# RF_Front_End.net
KiCad netlist of a schematic drawn in Altium Designer
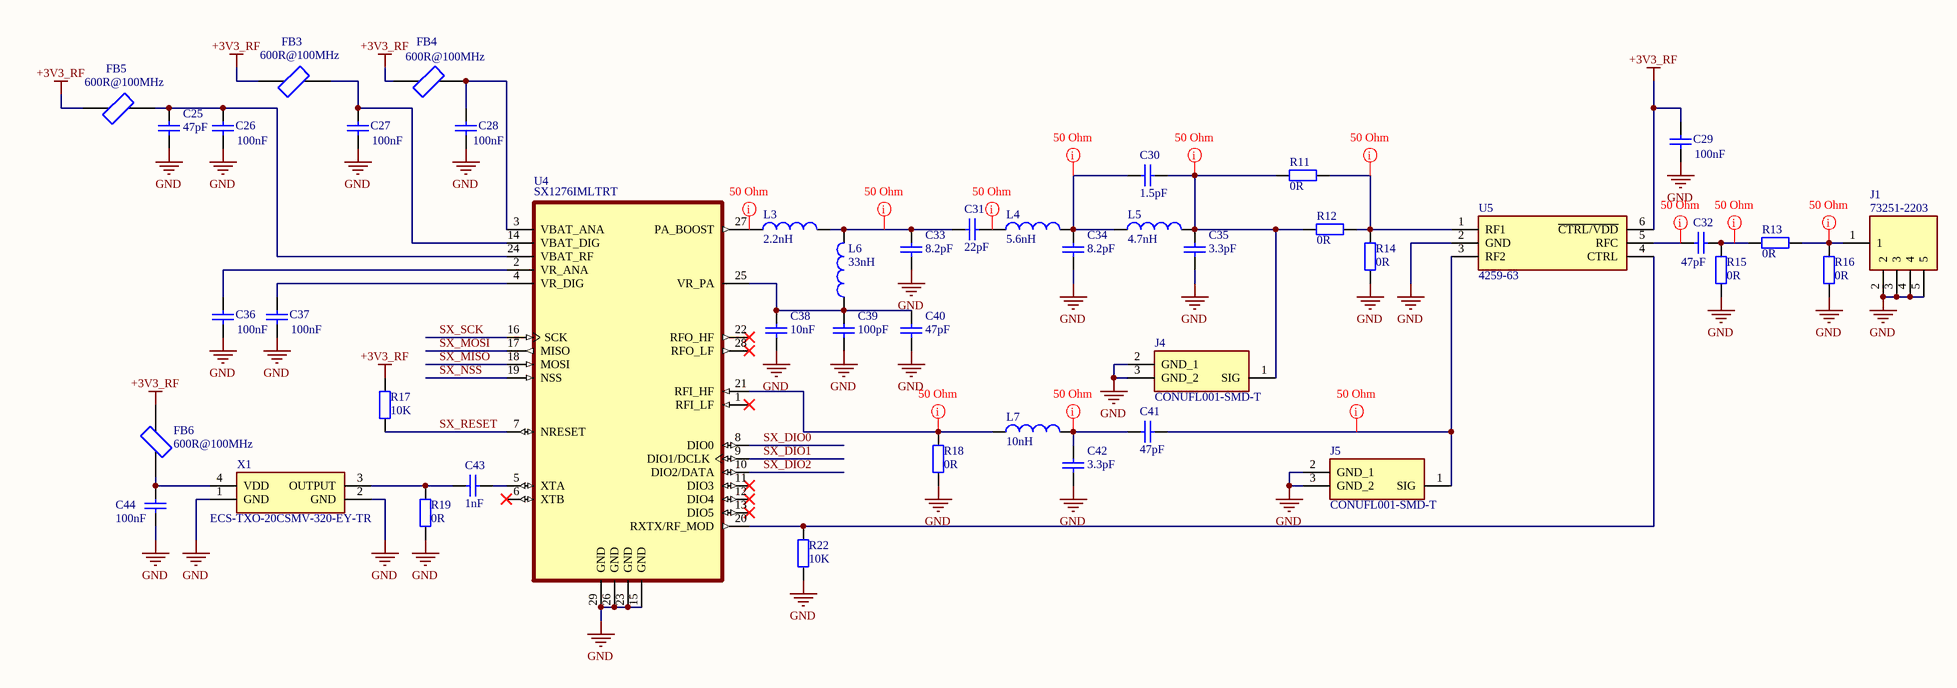
[diagram p0: RF Front End.SchDoc]

(export (version "E")
  (design (tool "Eeschema 10.0.6"))
  (components
    (comp (ref "C25")
      (value "47pF")
      (footprint "SMD-0402C")
      (description "Capacitor")
      (fields (field (name "PUBLISHER") "Altium Limited"))
      (libsource (lib "Miscellaneous Devices") (part "Cap"))
    )
    (comp (ref "C26")
      (value "100nF")
      (footprint "SMD-0402C")
      (description "Capacitor")
      (fields (field (name "PUBLISHER") "Altium Limited"))
      (libsource (lib "Miscellaneous Devices") (part "Cap"))
    )
    (comp (ref "C27")
      (value "100nF")
      (footprint "SMD-0402C")
      (description "Capacitor")
      (fields (field (name "PUBLISHER") "Altium Limited"))
      (libsource (lib "Miscellaneous Devices") (part "Cap"))
    )
    (comp (ref "C28")
      (value "100nF")
      (footprint "SMD-0402C")
      (description "Capacitor")
      (fields (field (name "PUBLISHER") "Altium Limited"))
      (libsource (lib "Miscellaneous Devices") (part "Cap"))
    )
    (comp (ref "C29")
      (value "100nF")
      (footprint "SMD-0402C")
      (description "Capacitor")
      (fields (field (name "PUBLISHER") "Altium Limited"))
      (libsource (lib "Miscellaneous Devices") (part "Cap"))
    )
    (comp (ref "C30")
      (value "1.5pF")
      (footprint "SMD-0402C")
      (description "Capacitor")
      (fields (field (name "PUBLISHER") "Altium Limited"))
      (libsource (lib "Miscellaneous Devices") (part "Cap"))
    )
    (comp (ref "C31")
      (value "22pF")
      (footprint "SMD-0402C")
      (description "Capacitor")
      (fields (field (name "PUBLISHER") "Altium Limited"))
      (libsource (lib "Miscellaneous Devices") (part "Cap"))
    )
    (comp (ref "C32")
      (value "47pF")
      (footprint "SMD-0402C")
      (description "Capacitor")
      (fields (field (name "PUBLISHER") "Altium Limited"))
      (libsource (lib "Miscellaneous Devices") (part "Cap"))
    )
    (comp (ref "C33")
      (value "8.2pF")
      (footprint "SMD-0402C")
      (description "Capacitor")
      (fields (field (name "PUBLISHER") "Altium Limited"))
      (libsource (lib "Miscellaneous Devices") (part "Cap"))
    )
    (comp (ref "C34")
      (value "8.2pF")
      (footprint "SMD-0402C")
      (description "Capacitor")
      (fields (field (name "PUBLISHER") "Altium Limited"))
      (libsource (lib "Miscellaneous Devices") (part "Cap"))
    )
    (comp (ref "C35")
      (value "3.3pF")
      (footprint "SMD-0402C")
      (description "Capacitor")
      (fields (field (name "PUBLISHER") "Altium Limited"))
      (libsource (lib "Miscellaneous Devices") (part "Cap"))
    )
    (comp (ref "C36")
      (value "100nF")
      (footprint "SMD-0402C")
      (description "Capacitor")
      (fields (field (name "PUBLISHER") "Altium Limited"))
      (libsource (lib "Miscellaneous Devices") (part "Cap"))
    )
    (comp (ref "C37")
      (value "100nF")
      (footprint "SMD-0402C")
      (description "Capacitor")
      (fields (field (name "PUBLISHER") "Altium Limited"))
      (libsource (lib "Miscellaneous Devices") (part "Cap"))
    )
    (comp (ref "C38")
      (value "10nF")
      (footprint "SMD-0402C")
      (description "Capacitor")
      (fields (field (name "PUBLISHER") "Altium Limited"))
      (libsource (lib "Miscellaneous Devices") (part "Cap"))
    )
    (comp (ref "C39")
      (value "100pF")
      (footprint "SMD-0402C")
      (description "Capacitor")
      (fields (field (name "PUBLISHER") "Altium Limited"))
      (libsource (lib "Miscellaneous Devices") (part "Cap"))
    )
    (comp (ref "C40")
      (value "47pF")
      (footprint "SMD-0402C")
      (description "Capacitor")
      (fields (field (name "PUBLISHER") "Altium Limited"))
      (libsource (lib "Miscellaneous Devices") (part "Cap"))
    )
    (comp (ref "C41")
      (value "47pF")
      (footprint "SMD-0402C")
      (description "Capacitor")
      (fields (field (name "PUBLISHER") "Altium Limited"))
      (libsource (lib "Miscellaneous Devices") (part "Cap"))
    )
    (comp (ref "C42")
      (value "3.3pF")
      (footprint "SMD-0402C")
      (description "Capacitor")
      (fields (field (name "PUBLISHER") "Altium Limited"))
      (libsource (lib "Miscellaneous Devices") (part "Cap"))
    )
    (comp (ref "C43")
      (value "1nF")
      (footprint "SMD-0402C")
      (description "Capacitor")
      (fields (field (name "PUBLISHER") "Altium Limited"))
      (libsource (lib "Miscellaneous Devices") (part "Cap"))
    )
    (comp (ref "C44")
      (value "100nF")
      (footprint "SMD-0402C")
      (description "Capacitor")
      (fields (field (name "PUBLISHER") "Altium Limited"))
      (libsource (lib "Miscellaneous Devices") (part "Cap"))
    )
    (comp (ref "FB3")
      (value "600R@100MHz")
      (footprint "0402 Ferrite Bead")
      (description "Ferrite Beads FERRITE BEAD 600 OHM 0402 1LN")
      (fields (field (name "MF") "Laird-Signal Integrity Products") (field (name "MP") "MI0805K400R-10"))
      (libsource (lib "Schematic_library") (part "Ferrite"))
    )
    (comp (ref "FB4")
      (value "600R@100MHz")
      (footprint "0402 Ferrite Bead")
      (description "Ferrite Beads FERRITE BEAD 600 OHM 0402 1LN")
      (fields (field (name "MF") "Laird-Signal Integrity Products") (field (name "MP") "MI0805K400R-10"))
      (libsource (lib "Schematic_library") (part "Ferrite"))
    )
    (comp (ref "FB5")
      (value "600R@100MHz")
      (footprint "0402 Ferrite Bead")
      (description "Ferrite Beads FERRITE BEAD 600 OHM 0402 1LN")
      (fields (field (name "MF") "Laird-Signal Integrity Products") (field (name "MP") "MI0805K400R-10"))
      (libsource (lib "Schematic_library") (part "Ferrite"))
    )
    (comp (ref "FB6")
      (value "600R@100MHz")
      (footprint "0402 Ferrite Bead")
      (description "Ferrite Beads FERRITE BEAD 600 OHM 0402 1LN")
      (fields (field (name "MF") "Laird-Signal Integrity Products") (field (name "MP") "MI0805K400R-10"))
      (libsource (lib "Schematic_library") (part "Ferrite"))
    )
    (comp (ref "J1")
      (value "73251-2203")
      (footprint "732512203")
      (description "RF Connectors / Coaxial Connectors Conn 50 Ohms, SMA Jack, Right-Angle PCB, Gold")
      (fields (field (name "MOUSER PART NUMBER") "538-73251-2203"))
      (libsource (lib "Schematic_library") (part "73251-2203"))
    )
    (comp (ref "J4")
      (value "CONUFL001-SMD-T")
      (footprint "SamacSys:CONUFL001SMDT")
      (description "Connector")
      (libsource (lib "Schematic_library") (part "CONUFL001-SMD-T"))
    )
    (comp (ref "J5")
      (value "CONUFL001-SMD-T")
      (footprint "SamacSys:CONUFL001SMDT")
      (description "Connector")
      (libsource (lib "Schematic_library") (part "CONUFL001-SMD-T"))
    )
    (comp (ref "L3")
      (value "2.2nH")
      (footprint "SMD-0402-RES")
      (description "Inductor")
      (fields (field (name "PUBLISHER") "Altium Limited"))
      (libsource (lib "Miscellaneous Devices") (part "Inductor"))
    )
    (comp (ref "L4")
      (value "5.6nH")
      (footprint "SMD-0402-RES")
      (description "Inductor")
      (fields (field (name "PUBLISHER") "Altium Limited"))
      (libsource (lib "Miscellaneous Devices") (part "Inductor"))
    )
    (comp (ref "L5")
      (value "4.7nH")
      (footprint "SMD-0402-RES")
      (description "Inductor")
      (fields (field (name "PUBLISHER") "Altium Limited"))
      (libsource (lib "Miscellaneous Devices") (part "Inductor"))
    )
    (comp (ref "L6")
      (value "33nH")
      (footprint "SMD-0402-RES")
      (description "Inductor")
      (fields (field (name "PUBLISHER") "Altium Limited"))
      (libsource (lib "Miscellaneous Devices") (part "Inductor"))
    )
    (comp (ref "L7")
      (value "10nH")
      (footprint "SMD-0402-RES")
      (description "Inductor")
      (fields (field (name "PUBLISHER") "Altium Limited"))
      (libsource (lib "Miscellaneous Devices") (part "Inductor"))
    )
    (comp (ref "R11")
      (value "0R")
      (footprint "SMD-0402-RES")
      (description "Resistor")
      (fields (field (name "PUBLISHER") "Altium Limited"))
      (libsource (lib "") (part "Res2_1"))
    )
    (comp (ref "R12")
      (value "0R")
      (footprint "SMD-0402-RES")
      (description "Resistor")
      (fields (field (name "PUBLISHER") "Altium Limited"))
      (libsource (lib "") (part "Res2_1"))
    )
    (comp (ref "R13")
      (value "0R")
      (footprint "SMD-0402-RES")
      (description "Resistor")
      (fields (field (name "PUBLISHER") "Altium Limited"))
      (libsource (lib "") (part "Res2_1"))
    )
    (comp (ref "R14")
      (value "0R")
      (footprint "SMD-0402-RES")
      (description "Resistor")
      (fields (field (name "PUBLISHER") "Altium Limited"))
      (libsource (lib "Miscellaneous Devices") (part "Res2"))
    )
    (comp (ref "R15")
      (value "0R")
      (footprint "SMD-0402-RES")
      (description "Resistor")
      (fields (field (name "PUBLISHER") "Altium Limited"))
      (libsource (lib "Miscellaneous Devices") (part "Res2"))
    )
    (comp (ref "R16")
      (value "0R")
      (footprint "SMD-0402-RES")
      (description "Resistor")
      (fields (field (name "PUBLISHER") "Altium Limited"))
      (libsource (lib "Miscellaneous Devices") (part "Res2"))
    )
    (comp (ref "R17")
      (value "10K")
      (footprint "SMD-0402-RES")
      (description "Resistor")
      (fields (field (name "PUBLISHER") "Altium Limited"))
      (libsource (lib "Miscellaneous Devices") (part "Res2"))
    )
    (comp (ref "R18")
      (value "0R")
      (footprint "SMD-0402-RES")
      (description "Resistor")
      (fields (field (name "PUBLISHER") "Altium Limited"))
      (libsource (lib "Miscellaneous Devices") (part "Res2"))
    )
    (comp (ref "R19")
      (value "0R")
      (footprint "SMD-0402-RES")
      (description "Resistor")
      (fields (field (name "PUBLISHER") "Altium Limited"))
      (libsource (lib "Miscellaneous Devices") (part "Res2"))
    )
    (comp (ref "R22")
      (value "10K")
      (footprint "SMD-0402-RES")
      (description "Resistor")
      (fields (field (name "PUBLISHER") "Altium Limited"))
      (libsource (lib "Miscellaneous Devices") (part "Res2"))
    )
    (comp (ref "U4")
      (value "SX1276IMLTRT")
      (footprint "SX1276IMLTRT")
      (description "IC RF TxRx Only 802.15.4 LoRaâ„¢ 137MHz ~ 1.02GHz 28-VQFN Exposed Pad")
      (fields (field (name "MF") "Semtech Corporation"))
      (libsource (lib "Schematic_library") (part "SX1276IMLTRT"))
    )
    (comp (ref "U5")
      (value "4259-63")
      (footprint "4259-63")
      (description "RF switch IC")
      (fields (field (name "MOUSER PART NUMBER") "81-4259-63"))
      (libsource (lib "Schematic_library") (part "4259-63"))
    )
    (comp (ref "X1")
      (value "ECS-TXO-20CSMV-320-EY-TR")
      (footprint "ECS-TXO-20CSMV-320-EY-TR")
      (description "TCXO Oscillators MultiVolt TCXO,32MHz,+/-2.5ppm,1.7V 3.465V,2.5 mA,-30 C 85 C, 2.00mm x 1.60mm")
      (fields (field (name "MOUSER PART NUMBER") "520-TXO20CSMV320EYTR"))
      (libsource (lib "Schematic_library") (part "ECS-TXO-20CSMV-320-EY-TR"))
    )
  )
  (nets
    (net (code "1") (name "+3V3_RF") (class "Default")
      (node (ref "C29") (pin "2") (pinfunction "2_2") (pintype "passive"))
      (node (ref "FB3") (pin "1") (pinfunction "1_1") (pintype "passive"))
      (node (ref "FB4") (pin "1") (pinfunction "1_1") (pintype "passive"))
      (node (ref "FB5") (pin "1") (pinfunction "1_1") (pintype "passive"))
      (node (ref "FB6") (pin "2") (pinfunction "2_2") (pintype "passive"))
      (node (ref "R17") (pin "2") (pinfunction "2_2") (pintype "passive"))
      (node (ref "U5") (pin "6") (pinfunction "~{CTRL/VDD}_6") (pintype "passive"))
    )
    (net (code "2") (name "/SX_DIO0") (class "Default")
      (node (ref "U4") (pin "8") (pinfunction "DIO0_8") (pintype "bidirectional"))
    )
    (net (code "3") (name "/SX_DIO1") (class "Default")
      (node (ref "U4") (pin "9") (pinfunction "DIO1/DCLK_9") (pintype "bidirectional"))
    )
    (net (code "4") (name "/SX_DIO2") (class "Default")
      (node (ref "U4") (pin "10") (pinfunction "DIO2/DATA_10") (pintype "bidirectional"))
    )
    (net (code "5") (name "/SX_MISO") (class "Default")
      (node (ref "U4") (pin "18") (pinfunction "MOSI_18") (pintype "input"))
    )
    (net (code "6") (name "/SX_MOSI") (class "Default")
      (node (ref "U4") (pin "17") (pinfunction "MISO_17") (pintype "output"))
    )
    (net (code "7") (name "/SX_NSS") (class "Default")
      (node (ref "U4") (pin "19") (pinfunction "NSS_19") (pintype "input"))
    )
    (net (code "8") (name "/SX_RESET") (class "Default")
      (node (ref "R17") (pin "1") (pinfunction "1_1") (pintype "passive"))
      (node (ref "U4") (pin "7") (pinfunction "NRESET_7") (pintype "bidirectional"))
    )
    (net (code "9") (name "/SX_SCK") (class "Default")
      (node (ref "U4") (pin "16") (pinfunction "SCK_16") (pintype "input"))
    )
    (net (code "10") (name "GND") (class "Default")
      (node (ref "C25") (pin "1") (pinfunction "1_1") (pintype "passive"))
      (node (ref "C26") (pin "1") (pinfunction "1_1") (pintype "passive"))
      (node (ref "C27") (pin "1") (pinfunction "1_1") (pintype "passive"))
      (node (ref "C28") (pin "1") (pinfunction "1_1") (pintype "passive"))
      (node (ref "C29") (pin "1") (pinfunction "1_1") (pintype "passive"))
      (node (ref "C33") (pin "1") (pinfunction "1_1") (pintype "passive"))
      (node (ref "C34") (pin "1") (pinfunction "1_1") (pintype "passive"))
      (node (ref "C35") (pin "1") (pinfunction "1_1") (pintype "passive"))
      (node (ref "C36") (pin "1") (pinfunction "1_1") (pintype "passive"))
      (node (ref "C37") (pin "1") (pinfunction "1_1") (pintype "passive"))
      (node (ref "C38") (pin "1") (pinfunction "1_1") (pintype "passive"))
      (node (ref "C39") (pin "1") (pinfunction "1_1") (pintype "passive"))
      (node (ref "C40") (pin "1") (pinfunction "1_1") (pintype "passive"))
      (node (ref "C42") (pin "1") (pinfunction "1_1") (pintype "passive"))
      (node (ref "C44") (pin "1") (pinfunction "1_1") (pintype "passive"))
      (node (ref "J1") (pin "2") (pinfunction "2_2") (pintype "passive"))
      (node (ref "J1") (pin "3") (pinfunction "3_3") (pintype "passive"))
      (node (ref "J1") (pin "4") (pinfunction "4_4") (pintype "passive"))
      (node (ref "J1") (pin "5") (pinfunction "5_5") (pintype "passive"))
      (node (ref "J4") (pin "2") (pinfunction "GND_1_2") (pintype "passive"))
      (node (ref "J4") (pin "3") (pinfunction "GND_2_3") (pintype "passive"))
      (node (ref "J5") (pin "2") (pinfunction "GND_1_2") (pintype "passive"))
      (node (ref "J5") (pin "3") (pinfunction "GND_2_3") (pintype "passive"))
      (node (ref "R14") (pin "1") (pinfunction "1_1") (pintype "passive"))
      (node (ref "R15") (pin "1") (pinfunction "1_1") (pintype "passive"))
      (node (ref "R16") (pin "1") (pinfunction "1_1") (pintype "passive"))
      (node (ref "R18") (pin "1") (pinfunction "1_1") (pintype "passive"))
      (node (ref "R19") (pin "1") (pinfunction "1_1") (pintype "passive"))
      (node (ref "R22") (pin "1") (pinfunction "1_1") (pintype "passive"))
      (node (ref "U4") (pin "15") (pinfunction "GND_15") (pintype "power_in"))
      (node (ref "U4") (pin "23") (pinfunction "GND_23") (pintype "power_in"))
      (node (ref "U4") (pin "26") (pinfunction "GND_26") (pintype "power_in"))
      (node (ref "U4") (pin "29") (pinfunction "GND_29") (pintype "power_in"))
      (node (ref "U5") (pin "2") (pinfunction "GND_2") (pintype "passive"))
      (node (ref "X1") (pin "1") (pinfunction "GND_1") (pintype "passive"))
      (node (ref "X1") (pin "2") (pinfunction "GND_2") (pintype "passive"))
    )
    (net (code "11") (name "Net-(C30-Pad2)") (class "Default")
      (node (ref "C30") (pin "2") (pinfunction "2_2") (pintype "passive"))
      (node (ref "C34") (pin "2") (pinfunction "2_2") (pintype "passive"))
      (node (ref "L4") (pin "2") (pinfunction "2_2") (pintype "passive"))
      (node (ref "L5") (pin "1") (pinfunction "1_1") (pintype "passive"))
    )
    (net (code "12") (name "Net-(C31-Pad1)") (class "Default")
      (node (ref "C31") (pin "1") (pinfunction "1_1") (pintype "passive"))
      (node (ref "L4") (pin "1") (pinfunction "1_1") (pintype "passive"))
    )
    (net (code "13") (name "Net-(C31-Pad2)") (class "Default")
      (node (ref "C31") (pin "2") (pinfunction "2_2") (pintype "passive"))
      (node (ref "C33") (pin "2") (pinfunction "2_2") (pintype "passive"))
      (node (ref "L3") (pin "2") (pinfunction "2_2") (pintype "passive"))
      (node (ref "L6") (pin "2") (pinfunction "2_2") (pintype "passive"))
    )
    (net (code "14") (name "Net-(C32-Pad1)") (class "Default")
      (node (ref "C32") (pin "1") (pinfunction "1_1") (pintype "passive"))
      (node (ref "R13") (pin "2") (pinfunction "2_2") (pintype "passive"))
      (node (ref "R15") (pin "2") (pinfunction "2_2") (pintype "passive"))
    )
    (net (code "15") (name "Net-(C41-Pad2)") (class "Default")
      (node (ref "C41") (pin "2") (pinfunction "2_2") (pintype "passive"))
      (node (ref "C42") (pin "2") (pinfunction "2_2") (pintype "passive"))
      (node (ref "L7") (pin "2") (pinfunction "2_2") (pintype "passive"))
    )
    (net (code "16") (name "Net-(J1-Pad1)") (class "Default")
      (node (ref "J1") (pin "1") (pinfunction "1_1") (pintype "passive"))
      (node (ref "R13") (pin "1") (pinfunction "1_1") (pintype "passive"))
      (node (ref "R16") (pin "2") (pinfunction "2_2") (pintype "passive"))
    )
    (net (code "17") (name "Net-(J4-SIG)") (class "Default")
      (node (ref "C30") (pin "1") (pinfunction "1_1") (pintype "passive"))
      (node (ref "C35") (pin "2") (pinfunction "2_2") (pintype "passive"))
      (node (ref "J4") (pin "1") (pinfunction "SIG_1") (pintype "passive"))
      (node (ref "L5") (pin "2") (pinfunction "2_2") (pintype "passive"))
      (node (ref "R11") (pin "2") (pinfunction "2_2") (pintype "passive"))
      (node (ref "R12") (pin "2") (pinfunction "2_2") (pintype "passive"))
    )
    (net (code "18") (name "Net-(J5-SIG)") (class "Default")
      (node (ref "C41") (pin "1") (pinfunction "1_1") (pintype "passive"))
      (node (ref "J5") (pin "1") (pinfunction "SIG_1") (pintype "passive"))
      (node (ref "U5") (pin "3") (pinfunction "RF2_3") (pintype "passive"))
    )
    (net (code "19") (name "Net-(U4-PA_BOOST)") (class "Default")
      (node (ref "L3") (pin "1") (pinfunction "1_1") (pintype "passive"))
      (node (ref "U4") (pin "27") (pinfunction "PA_BOOST_27") (pintype "output"))
    )
    (net (code "20") (name "Net-(U4-RFI_HF)") (class "Default")
      (node (ref "L7") (pin "1") (pinfunction "1_1") (pintype "passive"))
      (node (ref "R18") (pin "2") (pinfunction "2_2") (pintype "passive"))
      (node (ref "U4") (pin "21") (pinfunction "RFI_HF_21") (pintype "input"))
    )
    (net (code "21") (name "Net-(U4-RXTX{slash}RF_MOD)") (class "Default")
      (node (ref "R22") (pin "2") (pinfunction "2_2") (pintype "passive"))
      (node (ref "U4") (pin "20") (pinfunction "RXTX/RF_MOD_20") (pintype "output"))
      (node (ref "U5") (pin "4") (pinfunction "CTRL_4") (pintype "passive"))
    )
    (net (code "22") (name "Net-(U4-VBAT_ANA)") (class "Default")
      (node (ref "C28") (pin "2") (pinfunction "2_2") (pintype "passive"))
      (node (ref "FB4") (pin "2") (pinfunction "2_2") (pintype "passive"))
      (node (ref "U4") (pin "3") (pinfunction "VBAT_ANA_3") (pintype "power_in"))
    )
    (net (code "23") (name "Net-(U4-VBAT_DIG)") (class "Default")
      (node (ref "C27") (pin "2") (pinfunction "2_2") (pintype "passive"))
      (node (ref "FB3") (pin "2") (pinfunction "2_2") (pintype "passive"))
      (node (ref "U4") (pin "14") (pinfunction "VBAT_DIG_14") (pintype "power_in"))
    )
    (net (code "24") (name "Net-(U4-VBAT_RF)") (class "Default")
      (node (ref "C25") (pin "2") (pinfunction "2_2") (pintype "passive"))
      (node (ref "C26") (pin "2") (pinfunction "2_2") (pintype "passive"))
      (node (ref "FB5") (pin "2") (pinfunction "2_2") (pintype "passive"))
      (node (ref "U4") (pin "24") (pinfunction "VBAT_RF_24") (pintype "power_in"))
    )
    (net (code "25") (name "Net-(U4-VR_ANA)") (class "Default")
      (node (ref "C36") (pin "2") (pinfunction "2_2") (pintype "passive"))
      (node (ref "U4") (pin "2") (pinfunction "VR_ANA_2") (pintype "power_in"))
    )
    (net (code "26") (name "Net-(U4-VR_DIG)") (class "Default")
      (node (ref "C37") (pin "2") (pinfunction "2_2") (pintype "passive"))
      (node (ref "U4") (pin "4") (pinfunction "VR_DIG_4") (pintype "power_in"))
    )
    (net (code "27") (name "Net-(U4-VR_PA)") (class "Default")
      (node (ref "C38") (pin "2") (pinfunction "2_2") (pintype "passive"))
      (node (ref "C39") (pin "2") (pinfunction "2_2") (pintype "passive"))
      (node (ref "C40") (pin "2") (pinfunction "2_2") (pintype "passive"))
      (node (ref "L6") (pin "1") (pinfunction "1_1") (pintype "passive"))
      (node (ref "U4") (pin "25") (pinfunction "VR_PA_25") (pintype "power_in"))
    )
    (net (code "28") (name "Net-(U4-XTA)") (class "Default")
      (node (ref "C43") (pin "1") (pinfunction "1_1") (pintype "passive"))
      (node (ref "U4") (pin "5") (pinfunction "XTA_5") (pintype "bidirectional"))
    )
    (net (code "29") (name "Net-(U5-RF1)") (class "Default")
      (node (ref "R11") (pin "1") (pinfunction "1_1") (pintype "passive"))
      (node (ref "R12") (pin "1") (pinfunction "1_1") (pintype "passive"))
      (node (ref "R14") (pin "2") (pinfunction "2_2") (pintype "passive"))
      (node (ref "U5") (pin "1") (pinfunction "RF1_1") (pintype "passive"))
    )
    (net (code "30") (name "Net-(U5-RFC)") (class "Default")
      (node (ref "C32") (pin "2") (pinfunction "2_2") (pintype "passive"))
      (node (ref "U5") (pin "5") (pinfunction "RFC_5") (pintype "passive"))
    )
    (net (code "31") (name "Net-(X1-OUTPUT)") (class "Default")
      (node (ref "C43") (pin "2") (pinfunction "2_2") (pintype "passive"))
      (node (ref "R19") (pin "2") (pinfunction "2_2") (pintype "passive"))
      (node (ref "X1") (pin "3") (pinfunction "OUTPUT_3") (pintype "passive"))
    )
    (net (code "32") (name "Net-(X1-VDD)") (class "Default")
      (node (ref "C44") (pin "2") (pinfunction "2_2") (pintype "passive"))
      (node (ref "FB6") (pin "1") (pinfunction "1_1") (pintype "passive"))
      (node (ref "X1") (pin "4") (pinfunction "VDD_4") (pintype "passive"))
    )
    (net (code "33") (name "unconnected-(U4-DIO3-Pad11)") (class "Default")
      (node (ref "U4") (pin "11") (pinfunction "DIO3_11") (pintype "bidirectional+no_connect"))
    )
    (net (code "34") (name "unconnected-(U4-DIO4-Pad12)") (class "Default")
      (node (ref "U4") (pin "12") (pinfunction "DIO4_12") (pintype "bidirectional+no_connect"))
    )
    (net (code "35") (name "unconnected-(U4-DIO5-Pad13)") (class "Default")
      (node (ref "U4") (pin "13") (pinfunction "DIO5_13") (pintype "bidirectional+no_connect"))
    )
    (net (code "36") (name "unconnected-(U4-RFI_LF-Pad1)") (class "Default")
      (node (ref "U4") (pin "1") (pinfunction "RFI_LF_1") (pintype "input+no_connect"))
    )
    (net (code "37") (name "unconnected-(U4-RFO_HF-Pad22)") (class "Default")
      (node (ref "U4") (pin "22") (pinfunction "RFO_HF_22") (pintype "output+no_connect"))
    )
    (net (code "38") (name "unconnected-(U4-RFO_LF-Pad28)") (class "Default")
      (node (ref "U4") (pin "28") (pinfunction "RFO_LF_28") (pintype "output+no_connect"))
    )
    (net (code "39") (name "unconnected-(U4-XTB-Pad6)") (class "Default")
      (node (ref "U4") (pin "6") (pinfunction "XTB_6") (pintype "bidirectional+no_connect"))
    )
  )
)
